# gripper_board.net
KiCad netlist of a schematic drawn in EAGLE
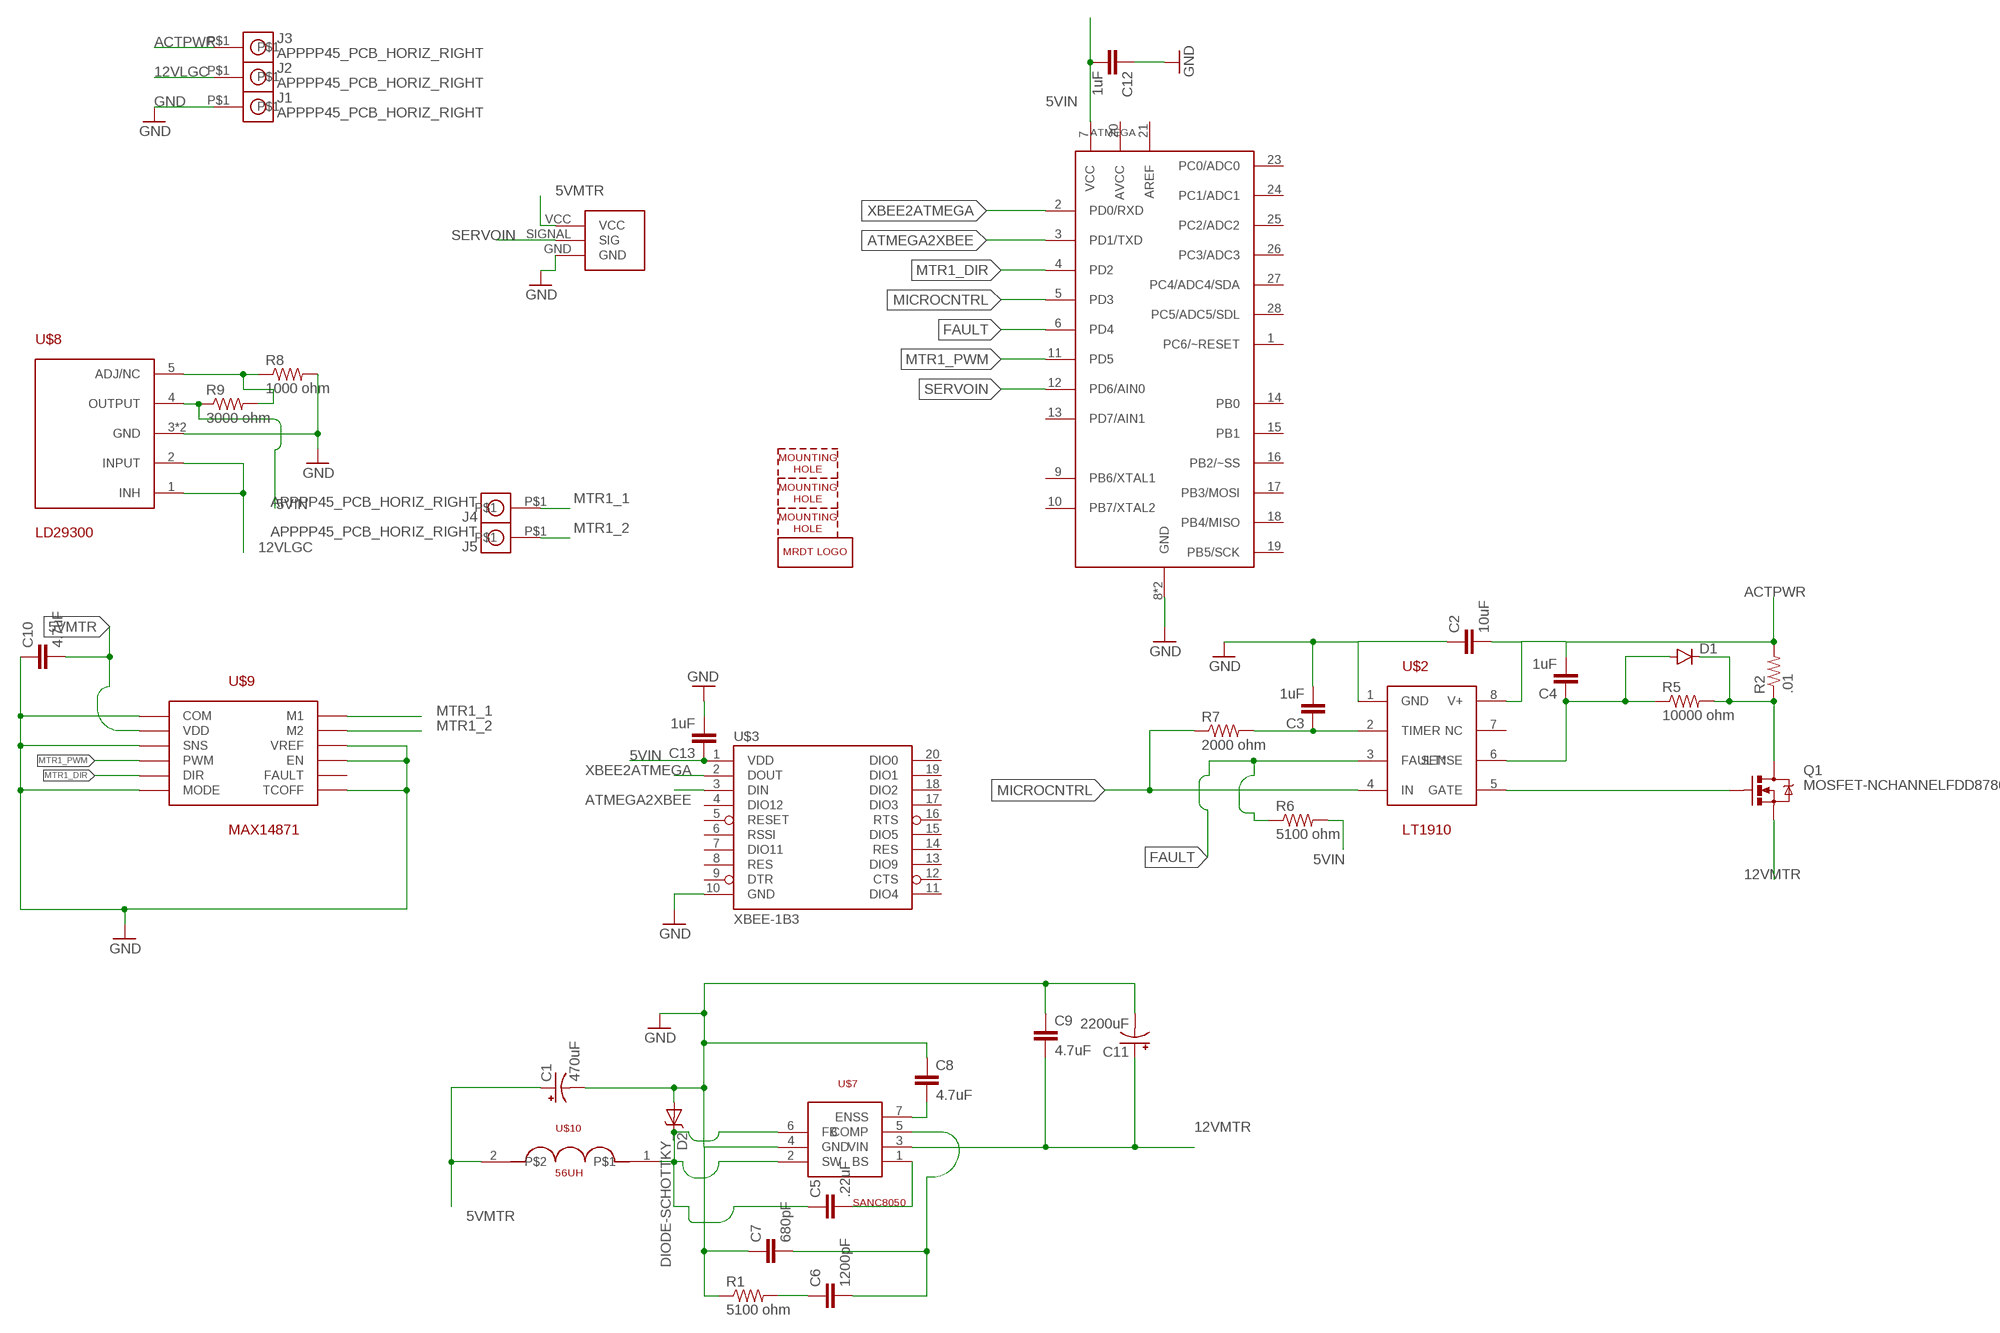
[diagram p0: schematic, sheet 1]

(export (version "E")
  (design (tool "Eeschema 10.0.6"))
  (components
    (comp (ref "ATMEGA")
      (value "Q_ATMEGA328P")
      (footprint "eagle-import:DIP28")
      (libsource (lib "eagle-import") (part "Q_ATMEGA328P"))
    )
    (comp (ref "C1")
      (value "470uF")
      (footprint "eagle-import:PANASONIC_H13")
      (libsource (lib "eagle-import") (part "100UF-ELECT"))
    )
    (comp (ref "C2")
      (value "10uF")
      (footprint "eagle-import:0603-CAP")
      (libsource (lib "eagle-import") (part "CAP0603-CAP"))
    )
    (comp (ref "C3")
      (value "1uF")
      (footprint "eagle-import:0603-CAP")
      (libsource (lib "eagle-import") (part "CAP0603-CAP"))
    )
    (comp (ref "C4")
      (value "1uF")
      (footprint "eagle-import:0603-CAP")
      (libsource (lib "eagle-import") (part "CAP0603-CAP"))
    )
    (comp (ref "C5")
      (value ".22uF")
      (footprint "eagle-import:1206")
      (libsource (lib "eagle-import") (part "1.0UF50V10%(1206)"))
    )
    (comp (ref "C6")
      (value "1200pF")
      (footprint "eagle-import:1206")
      (libsource (lib "eagle-import") (part "1.0UF50V10%(1206)"))
    )
    (comp (ref "C7")
      (value "680pF")
      (footprint "eagle-import:1206")
      (libsource (lib "eagle-import") (part "1.0UF50V10%(1206)"))
    )
    (comp (ref "C8")
      (value "4.7uF")
      (footprint "eagle-import:1206")
      (libsource (lib "eagle-import") (part "1.0UF50V10%(1206)"))
    )
    (comp (ref "C9")
      (value "4.7uF")
      (footprint "eagle-import:1206")
      (libsource (lib "eagle-import") (part "1.0UF50V10%(1206)"))
    )
    (comp (ref "C10")
      (value "4.7uF")
      (footprint "eagle-import:1206")
      (libsource (lib "eagle-import") (part "1.0UF50V10%(1206)"))
    )
    (comp (ref "C11")
      (value "2200uF")
      (footprint "eagle-import:C_16MM")
      (libsource (lib "eagle-import") (part "C_108CKH050M"))
    )
    (comp (ref "C12")
      (value "1uF")
      (footprint "eagle-import:0603-CAP")
      (libsource (lib "eagle-import") (part "CAP0603-CAP"))
    )
    (comp (ref "C13")
      (value "1uF")
      (footprint "eagle-import:0603-CAP")
      (libsource (lib "eagle-import") (part "CAP0603-CAP"))
    )
    (comp (ref "D1")
      (value "DIODESMA")
      (footprint "eagle-import:SMA-DIODE")
      (libsource (lib "eagle-import") (part "DIODESMA"))
    )
    (comp (ref "D2")
      (value "DIODE-SCHOTTKY_")
      (footprint "eagle-import:SMA-DIODE")
      (libsource (lib "eagle-import") (part "DIODE-SCHOTTKY_"))
    )
    (comp (ref "H1")
      (value "MOUNTING_HOLE#4")
      (footprint "eagle-import:#4_SCREW")
      (libsource (lib "eagle-import") (part "MOUNTING_HOLE#4"))
    )
    (comp (ref "H2")
      (value "MOUNTING_HOLE#4")
      (footprint "eagle-import:#4_SCREW")
      (libsource (lib "eagle-import") (part "MOUNTING_HOLE#4"))
    )
    (comp (ref "H3")
      (value "MOUNTING_HOLE#4")
      (footprint "eagle-import:#4_SCREW")
      (libsource (lib "eagle-import") (part "MOUNTING_HOLE#4"))
    )
    (comp (ref "J1")
      (value "APPPP45_PCB_HORIZ_RIGHT")
      (footprint "eagle-import:APP45_PCB_HORIZ_RIGHT")
      (libsource (lib "eagle-import") (part "APPPP45_PCB_HORIZ_RIGHT"))
    )
    (comp (ref "J2")
      (value "APPPP45_PCB_HORIZ_RIGHT")
      (footprint "eagle-import:APP45_PCB_HORIZ_RIGHT")
      (libsource (lib "eagle-import") (part "APPPP45_PCB_HORIZ_RIGHT"))
    )
    (comp (ref "J3")
      (value "APPPP45_PCB_HORIZ_RIGHT")
      (footprint "eagle-import:APP45_PCB_HORIZ_RIGHT")
      (libsource (lib "eagle-import") (part "APPPP45_PCB_HORIZ_RIGHT"))
    )
    (comp (ref "J4")
      (value "APPPP45_PCB_HORIZ_RIGHT")
      (footprint "eagle-import:APP45_PCB_HORIZ_RIGHT")
      (libsource (lib "eagle-import") (part "APPPP45_PCB_HORIZ_RIGHT"))
    )
    (comp (ref "J5")
      (value "APPPP45_PCB_HORIZ_RIGHT")
      (footprint "eagle-import:APP45_PCB_HORIZ_RIGHT")
      (libsource (lib "eagle-import") (part "APPPP45_PCB_HORIZ_RIGHT"))
    )
    (comp (ref "LOGO1")
      (value "MRDT_LOGO")
      (footprint "eagle-import:MRDT_LOGO")
      (libsource (lib "eagle-import") (part "MRDT_LOGO"))
    )
    (comp (ref "Q1")
      (value "MOSFET-NCHANNELFDD8780")
      (footprint "eagle-import:DPAK")
      (libsource (lib "eagle-import") (part "MOSFET-NCHANNELFDD8780"))
    )
    (comp (ref "R1")
      (value "5100 ohm")
      (footprint "eagle-import:0603-RES")
      (libsource (lib "eagle-import") (part "RESISTOR0603-RES"))
    )
    (comp (ref "R2")
      (value ".01")
      (footprint "eagle-import:AXIAL-0.3")
      (libsource (lib "eagle-import") (part "SparkFun-Resistors_RESISTORAXIAL-0.3"))
    )
    (comp (ref "R5")
      (value "10000 ohm")
      (footprint "eagle-import:0603-RES")
      (libsource (lib "eagle-import") (part "RESISTOR0603-RES"))
    )
    (comp (ref "R6")
      (value "5100 ohm")
      (footprint "eagle-import:0603-RES")
      (libsource (lib "eagle-import") (part "RESISTOR0603-RES"))
    )
    (comp (ref "R7")
      (value "2000 ohm")
      (footprint "eagle-import:0603-RES")
      (libsource (lib "eagle-import") (part "RESISTOR0603-RES"))
    )
    (comp (ref "R8")
      (value "1000 ohm")
      (footprint "eagle-import:0603-RES")
      (libsource (lib "eagle-import") (part "RESISTOR0603-RES"))
    )
    (comp (ref "R9")
      (value "3000 ohm")
      (footprint "eagle-import:0603-RES")
      (libsource (lib "eagle-import") (part "RESISTOR0603-RES"))
    )
    (comp (ref "U$1")
      (value "SERVO")
      (footprint "eagle-import:SERVO_JACK")
      (libsource (lib "eagle-import") (part "SERVO"))
    )
    (comp (ref "U$2")
      (value "LT1910")
      (footprint "eagle-import:SOIC8")
      (libsource (lib "eagle-import") (part "LT1910"))
    )
    (comp (ref "U$3")
      (value "XBEE-1B3")
      (footprint "eagle-import:XBEE-SMD")
      (libsource (lib "eagle-import") (part "XBEE-1B3"))
    )
    (comp (ref "U$7")
      (value "SANC8050")
      (footprint "eagle-import:TO-220-7")
      (libsource (lib "eagle-import") (part "SANC8050"))
    )
    (comp (ref "U$8")
      (value "LD29300")
      (footprint "eagle-import:P2PAK")
      (libsource (lib "eagle-import") (part "LD29300"))
    )
    (comp (ref "U$9")
      (value "MAX14871")
      (footprint "eagle-import:TSSOP-16")
      (libsource (lib "eagle-import") (part "MAX14871"))
    )
    (comp (ref "U$10")
      (value "56UH")
      (footprint "eagle-import:1210")
      (libsource (lib "eagle-import") (part "56UH"))
    )
  )
  (nets
    (net (code "1") (name "/5VIN") (class "Default")
      (node (ref "ATMEGA") (pin "7") (pinfunction "VCC_7") (pintype "bidirectional"))
      (node (ref "C12") (pin "2") (pinfunction "2_2") (pintype "passive"))
      (node (ref "C13") (pin "1") (pinfunction "1_1") (pintype "passive"))
      (node (ref "R6") (pin "2") (pinfunction "2_2") (pintype "passive"))
      (node (ref "R9") (pin "1") (pinfunction "1_1") (pintype "passive"))
      (node (ref "U$3") (pin "1") (pinfunction "VDD_1") (pintype "power_in"))
      (node (ref "U$8") (pin "4") (pinfunction "OUTPUT_4") (pintype "bidirectional"))
    )
    (net (code "2") (name "/12VLGC") (class "Default")
      (node (ref "J2") (pin "P$1") (pinfunction "P$1_P$1") (pintype "bidirectional"))
      (node (ref "U$8") (pin "1") (pinfunction "INH_1") (pintype "bidirectional"))
      (node (ref "U$8") (pin "2") (pinfunction "INPUT_2") (pintype "bidirectional"))
    )
    (net (code "3") (name "/12VMTR") (class "Default")
      (node (ref "C11") (pin "+") (pinfunction "+_+") (pintype "passive"))
      (node (ref "C9") (pin "2") (pinfunction "2_2") (pintype "passive"))
      (node (ref "Q1") (pin "3") (pinfunction "S_3") (pintype "passive"))
      (node (ref "U$7") (pin "3") (pinfunction "VIN_3") (pintype "bidirectional"))
    )
    (net (code "4") (name "/ACTPWR") (class "Default")
      (node (ref "C2") (pin "2") (pinfunction "2_2") (pintype "passive"))
      (node (ref "C4") (pin "2") (pinfunction "2_2") (pintype "passive"))
      (node (ref "J3") (pin "P$1") (pinfunction "P$1_P$1") (pintype "bidirectional"))
      (node (ref "R2") (pin "P$2") (pinfunction "2_P$2") (pintype "passive"))
      (node (ref "U$2") (pin "8") (pinfunction "V+_8") (pintype "bidirectional"))
    )
    (net (code "5") (name "/MTR1_1") (class "Default")
      (node (ref "J4") (pin "P$1") (pinfunction "P$1_P$1") (pintype "bidirectional"))
      (node (ref "U$9") (pin "2") (pinfunction "M1_2") (pintype "bidirectional"))
      (node (ref "U$9") (pin "3") (pinfunction "M1_3") (pintype "bidirectional"))
    )
    (net (code "6") (name "/MTR1_2") (class "Default")
      (node (ref "J5") (pin "P$1") (pinfunction "P$1_P$1") (pintype "bidirectional"))
      (node (ref "U$9") (pin "14") (pinfunction "M2_14") (pintype "bidirectional"))
      (node (ref "U$9") (pin "15") (pinfunction "M2_15") (pintype "bidirectional"))
    )
    (net (code "7") (name "5VMTR") (class "Default")
      (node (ref "C1") (pin "+") (pinfunction "+_+") (pintype "passive"))
      (node (ref "C10") (pin "2") (pinfunction "2_2") (pintype "passive"))
      (node (ref "U$1") (pin "VCC") (pinfunction "VCC_VCC") (pintype "bidirectional"))
      (node (ref "U$10") (pin "2") (pinfunction "P$2_2") (pintype "bidirectional"))
      (node (ref "U$9") (pin "13") (pinfunction "VDD_13") (pintype "bidirectional"))
      (node (ref "U$9") (pin "4") (pinfunction "VDD_4") (pintype "bidirectional"))
    )
    (net (code "8") (name "ATMEGA2XBEE") (class "Default")
      (node (ref "ATMEGA") (pin "3") (pinfunction "PD1/TXD_3") (pintype "bidirectional"))
      (node (ref "U$3") (pin "3") (pinfunction "DIN_3") (pintype "input"))
    )
    (net (code "9") (name "FAULT") (class "Default")
      (node (ref "ATMEGA") (pin "6") (pinfunction "PD4_6") (pintype "bidirectional"))
      (node (ref "R6") (pin "1") (pinfunction "1_1") (pintype "passive"))
      (node (ref "U$2") (pin "3") (pinfunction "FAULT*_3") (pintype "bidirectional"))
    )
    (net (code "10") (name "GND") (class "Default")
      (node (ref "ATMEGA") (pin "22") (pinfunction "GND_22") (pintype "bidirectional"))
      (node (ref "ATMEGA") (pin "8") (pinfunction "GND_8") (pintype "bidirectional"))
      (node (ref "C1") (pin "-") (pinfunction "-_-") (pintype "passive"))
      (node (ref "C10") (pin "1") (pinfunction "1_1") (pintype "passive"))
      (node (ref "C11") (pin "GND") (pinfunction "-_GND") (pintype "passive"))
      (node (ref "C12") (pin "1") (pinfunction "1_1") (pintype "passive"))
      (node (ref "C13") (pin "2") (pinfunction "2_2") (pintype "passive"))
      (node (ref "C2") (pin "1") (pinfunction "1_1") (pintype "passive"))
      (node (ref "C3") (pin "2") (pinfunction "2_2") (pintype "passive"))
      (node (ref "C7") (pin "1") (pinfunction "1_1") (pintype "passive"))
      (node (ref "C8") (pin "1") (pinfunction "1_1") (pintype "passive"))
      (node (ref "C9") (pin "1") (pinfunction "1_1") (pintype "passive"))
      (node (ref "D2") (pin "A") (pinfunction "A_A") (pintype "passive"))
      (node (ref "J1") (pin "P$1") (pinfunction "P$1_P$1") (pintype "bidirectional"))
      (node (ref "R1") (pin "1") (pinfunction "1_1") (pintype "passive"))
      (node (ref "R8") (pin "2") (pinfunction "2_2") (pintype "passive"))
      (node (ref "U$1") (pin "GND") (pinfunction "GND_GND") (pintype "bidirectional"))
      (node (ref "U$2") (pin "1") (pinfunction "GND_1") (pintype "bidirectional"))
      (node (ref "U$3") (pin "10") (pinfunction "GND_10") (pintype "power_in"))
      (node (ref "U$7") (pin "4") (pinfunction "GND_4") (pintype "bidirectional"))
      (node (ref "U$8") (pin "3") (pinfunction "GND_3") (pintype "bidirectional"))
      (node (ref "U$8") (pin "P$1") (pinfunction "GND_P$1") (pintype "bidirectional"))
      (node (ref "U$9") (pin "1") (pinfunction "COM_1") (pintype "bidirectional"))
      (node (ref "U$9") (pin "11") (pinfunction "EN_11") (pintype "bidirectional"))
      (node (ref "U$9") (pin "12") (pinfunction "VREF_12") (pintype "bidirectional"))
      (node (ref "U$9") (pin "16") (pinfunction "COM_16") (pintype "bidirectional"))
      (node (ref "U$9") (pin "5") (pinfunction "SNS_5") (pintype "bidirectional"))
      (node (ref "U$9") (pin "8") (pinfunction "MODE_8") (pintype "bidirectional"))
      (node (ref "U$9") (pin "9") (pinfunction "TCOFF_9") (pintype "bidirectional"))
    )
    (net (code "11") (name "MICROCNTRL") (class "Default")
      (node (ref "ATMEGA") (pin "5") (pinfunction "PD3_5") (pintype "bidirectional"))
      (node (ref "R7") (pin "1") (pinfunction "1_1") (pintype "passive"))
      (node (ref "U$2") (pin "4") (pinfunction "IN_4") (pintype "bidirectional"))
    )
    (net (code "12") (name "MTR1_DIR") (class "Default")
      (node (ref "ATMEGA") (pin "4") (pinfunction "PD2_4") (pintype "bidirectional"))
      (node (ref "U$9") (pin "7") (pinfunction "DIR_7") (pintype "bidirectional"))
    )
    (net (code "13") (name "MTR1_PWM") (class "Default")
      (node (ref "ATMEGA") (pin "11") (pinfunction "PD5_11") (pintype "bidirectional"))
      (node (ref "U$9") (pin "6") (pinfunction "PWM_6") (pintype "bidirectional"))
    )
    (net (code "14") (name "Net-(C6-Pad1)") (class "Default")
      (node (ref "C6") (pin "1") (pinfunction "1_1") (pintype "passive"))
      (node (ref "R1") (pin "2") (pinfunction "2_2") (pintype "passive"))
    )
    (net (code "15") (name "Net-(Q1-D)") (class "Default")
      (node (ref "D1") (pin "C") (pinfunction "C_C") (pintype "passive"))
      (node (ref "Q1") (pin "4") (pinfunction "D_4") (pintype "passive"))
      (node (ref "R2") (pin "P$1") (pinfunction "1_P$1") (pintype "passive"))
      (node (ref "R5") (pin "2") (pinfunction "2_2") (pintype "passive"))
    )
    (net (code "16") (name "Net-(Q1-G)") (class "Default")
      (node (ref "Q1") (pin "1") (pinfunction "G_1") (pintype "passive"))
      (node (ref "U$2") (pin "5") (pinfunction "GATE_5") (pintype "bidirectional"))
    )
    (net (code "17") (name "Net-(U$2-SENSE)") (class "Default")
      (node (ref "C4") (pin "1") (pinfunction "1_1") (pintype "passive"))
      (node (ref "D1") (pin "A") (pinfunction "A_A") (pintype "passive"))
      (node (ref "R5") (pin "1") (pinfunction "1_1") (pintype "passive"))
      (node (ref "U$2") (pin "6") (pinfunction "SENSE_6") (pintype "bidirectional"))
    )
    (net (code "18") (name "Net-(U$2-TIMER)") (class "Default")
      (node (ref "C3") (pin "1") (pinfunction "1_1") (pintype "passive"))
      (node (ref "R7") (pin "2") (pinfunction "2_2") (pintype "passive"))
      (node (ref "U$2") (pin "2") (pinfunction "TIMER_2") (pintype "bidirectional"))
    )
    (net (code "19") (name "Net-(U$7-BS)") (class "Default")
      (node (ref "C5") (pin "2") (pinfunction "2_2") (pintype "passive"))
      (node (ref "U$7") (pin "1") (pinfunction "BS_1") (pintype "bidirectional"))
    )
    (net (code "20") (name "Net-(U$7-COMP)") (class "Default")
      (node (ref "C6") (pin "2") (pinfunction "2_2") (pintype "passive"))
      (node (ref "C7") (pin "2") (pinfunction "2_2") (pintype "passive"))
      (node (ref "U$7") (pin "5") (pinfunction "COMP_5") (pintype "bidirectional"))
    )
    (net (code "21") (name "Net-(U$7-ENSS)") (class "Default")
      (node (ref "C8") (pin "2") (pinfunction "2_2") (pintype "passive"))
      (node (ref "U$7") (pin "7") (pinfunction "ENSS_7") (pintype "bidirectional"))
    )
    (net (code "22") (name "Net-(U$8-ADJ{slash}NC)") (class "Default")
      (node (ref "R8") (pin "1") (pinfunction "1_1") (pintype "passive"))
      (node (ref "R9") (pin "2") (pinfunction "2_2") (pintype "passive"))
      (node (ref "U$8") (pin "5") (pinfunction "ADJ/NC_5") (pintype "bidirectional"))
    )
    (net (code "23") (name "Net-(U$10-P$1)") (class "Default")
      (node (ref "C5") (pin "1") (pinfunction "1_1") (pintype "passive"))
      (node (ref "D2") (pin "C") (pinfunction "C_C") (pintype "passive"))
      (node (ref "U$10") (pin "1") (pinfunction "P$1_1") (pintype "bidirectional"))
      (node (ref "U$7") (pin "2") (pinfunction "SW_2") (pintype "bidirectional"))
      (node (ref "U$7") (pin "6") (pinfunction "FB_6") (pintype "bidirectional"))
    )
    (net (code "24") (name "SERVOIN") (class "Default")
      (node (ref "ATMEGA") (pin "12") (pinfunction "PD6/AIN0_12") (pintype "bidirectional"))
      (node (ref "U$1") (pin "SIGNAL") (pinfunction "SIG_SIGNAL") (pintype "bidirectional"))
    )
    (net (code "25") (name "XBEE2ATMEGA") (class "Default")
      (node (ref "ATMEGA") (pin "2") (pinfunction "PD0/RXD_2") (pintype "bidirectional"))
      (node (ref "U$3") (pin "2") (pinfunction "DOUT_2") (pintype "output"))
    )
    (net (code "26") (name "unconnected-(ATMEGA-AREF-Pad21)") (class "Default")
      (node (ref "ATMEGA") (pin "21") (pinfunction "AREF_21") (pintype "bidirectional"))
    )
    (net (code "27") (name "unconnected-(ATMEGA-AVCC-Pad20)") (class "Default")
      (node (ref "ATMEGA") (pin "20") (pinfunction "AVCC_20") (pintype "bidirectional"))
    )
    (net (code "28") (name "unconnected-(ATMEGA-PB0-Pad14)") (class "Default")
      (node (ref "ATMEGA") (pin "14") (pinfunction "PB0_14") (pintype "bidirectional"))
    )
    (net (code "29") (name "unconnected-(ATMEGA-PB1-Pad15)") (class "Default")
      (node (ref "ATMEGA") (pin "15") (pinfunction "PB1_15") (pintype "bidirectional"))
    )
    (net (code "30") (name "unconnected-(ATMEGA-PB2{slash}~{SS}-Pad16)") (class "Default")
      (node (ref "ATMEGA") (pin "16") (pinfunction "PB2/~{SS}_16") (pintype "bidirectional"))
    )
    (net (code "31") (name "unconnected-(ATMEGA-PB3{slash}MOSI-Pad17)") (class "Default")
      (node (ref "ATMEGA") (pin "17") (pinfunction "PB3/MOSI_17") (pintype "bidirectional"))
    )
    (net (code "32") (name "unconnected-(ATMEGA-PB4{slash}MISO-Pad18)") (class "Default")
      (node (ref "ATMEGA") (pin "18") (pinfunction "PB4/MISO_18") (pintype "bidirectional"))
    )
    (net (code "33") (name "unconnected-(ATMEGA-PB5{slash}SCK-Pad19)") (class "Default")
      (node (ref "ATMEGA") (pin "19") (pinfunction "PB5/SCK_19") (pintype "bidirectional"))
    )
    (net (code "34") (name "unconnected-(ATMEGA-PB6{slash}XTAL1-Pad9)") (class "Default")
      (node (ref "ATMEGA") (pin "9") (pinfunction "PB6/XTAL1_9") (pintype "bidirectional"))
    )
    (net (code "35") (name "unconnected-(ATMEGA-PB7{slash}XTAL2-Pad10)") (class "Default")
      (node (ref "ATMEGA") (pin "10") (pinfunction "PB7/XTAL2_10") (pintype "bidirectional"))
    )
    (net (code "36") (name "unconnected-(ATMEGA-PC0{slash}ADC0-Pad23)") (class "Default")
      (node (ref "ATMEGA") (pin "23") (pinfunction "PC0/ADC0_23") (pintype "bidirectional"))
    )
    (net (code "37") (name "unconnected-(ATMEGA-PC1{slash}ADC1-Pad24)") (class "Default")
      (node (ref "ATMEGA") (pin "24") (pinfunction "PC1/ADC1_24") (pintype "bidirectional"))
    )
    (net (code "38") (name "unconnected-(ATMEGA-PC2{slash}ADC2-Pad25)") (class "Default")
      (node (ref "ATMEGA") (pin "25") (pinfunction "PC2/ADC2_25") (pintype "bidirectional"))
    )
    (net (code "39") (name "unconnected-(ATMEGA-PC3{slash}ADC3-Pad26)") (class "Default")
      (node (ref "ATMEGA") (pin "26") (pinfunction "PC3/ADC3_26") (pintype "bidirectional"))
    )
    (net (code "40") (name "unconnected-(ATMEGA-PC4{slash}ADC4{slash}SDA-Pad27)") (class "Default")
      (node (ref "ATMEGA") (pin "27") (pinfunction "PC4/ADC4/SDA_27") (pintype "bidirectional"))
    )
    (net (code "41") (name "unconnected-(ATMEGA-PC5{slash}ADC5{slash}SDL-Pad28)") (class "Default")
      (node (ref "ATMEGA") (pin "28") (pinfunction "PC5/ADC5/SDL_28") (pintype "bidirectional"))
    )
    (net (code "42") (name "unconnected-(ATMEGA-PC6{slash}~{RESET}-Pad1)") (class "Default")
      (node (ref "ATMEGA") (pin "1") (pinfunction "PC6/~{RESET}_1") (pintype "bidirectional"))
    )
    (net (code "43") (name "unconnected-(ATMEGA-PD7{slash}AIN1-Pad13)") (class "Default")
      (node (ref "ATMEGA") (pin "13") (pinfunction "PD7/AIN1_13") (pintype "bidirectional"))
    )
    (net (code "44") (name "unconnected-(U$2-NC-Pad7)") (class "Default")
      (node (ref "U$2") (pin "7") (pinfunction "NC_7") (pintype "bidirectional"))
    )
    (net (code "45") (name "unconnected-(U$3-CTS-Pad12)") (class "Default")
      (node (ref "U$3") (pin "12") (pinfunction "CTS_12") (pintype "output"))
    )
    (net (code "46") (name "unconnected-(U$3-DIO0-Pad20)") (class "Default")
      (node (ref "U$3") (pin "20") (pinfunction "DIO0_20") (pintype "bidirectional"))
    )
    (net (code "47") (name "unconnected-(U$3-DIO1-Pad19)") (class "Default")
      (node (ref "U$3") (pin "19") (pinfunction "DIO1_19") (pintype "bidirectional"))
    )
    (net (code "48") (name "unconnected-(U$3-DIO2-Pad18)") (class "Default")
      (node (ref "U$3") (pin "18") (pinfunction "DIO2_18") (pintype "bidirectional"))
    )
    (net (code "49") (name "unconnected-(U$3-DIO3-Pad17)") (class "Default")
      (node (ref "U$3") (pin "17") (pinfunction "DIO3_17") (pintype "bidirectional"))
    )
    (net (code "50") (name "unconnected-(U$3-DIO4-Pad11)") (class "Default")
      (node (ref "U$3") (pin "11") (pinfunction "DIO4_11") (pintype "bidirectional"))
    )
    (net (code "51") (name "unconnected-(U$3-DIO5-Pad15)") (class "Default")
      (node (ref "U$3") (pin "15") (pinfunction "DIO5_15") (pintype "bidirectional"))
    )
    (net (code "52") (name "unconnected-(U$3-DIO9-Pad13)") (class "Default")
      (node (ref "U$3") (pin "13") (pinfunction "DIO9_13") (pintype "bidirectional"))
    )
    (net (code "53") (name "unconnected-(U$3-DIO11-Pad7)") (class "Default")
      (node (ref "U$3") (pin "7") (pinfunction "DIO11_7") (pintype "bidirectional"))
    )
    (net (code "54") (name "unconnected-(U$3-DIO12-Pad4)") (class "Default")
      (node (ref "U$3") (pin "4") (pinfunction "DIO12_4") (pintype "bidirectional"))
    )
    (net (code "55") (name "unconnected-(U$3-DTR-Pad9)") (class "Default")
      (node (ref "U$3") (pin "9") (pinfunction "DTR_9") (pintype "bidirectional"))
    )
    (net (code "56") (name "unconnected-(U$3-RES-Pad8)") (class "Default")
      (node (ref "U$3") (pin "8") (pinfunction "RES_8") (pintype "bidirectional"))
    )
    (net (code "57") (name "unconnected-(U$3-RES-Pad14)") (class "Default")
      (node (ref "U$3") (pin "14") (pinfunction "RES_14") (pintype "bidirectional"))
    )
    (net (code "58") (name "unconnected-(U$3-RESET-Pad5)") (class "Default")
      (node (ref "U$3") (pin "5") (pinfunction "RESET_5") (pintype "input"))
    )
    (net (code "59") (name "unconnected-(U$3-RSSI-Pad6)") (class "Default")
      (node (ref "U$3") (pin "6") (pinfunction "RSSI_6") (pintype "bidirectional"))
    )
    (net (code "60") (name "unconnected-(U$3-RTS-Pad16)") (class "Default")
      (node (ref "U$3") (pin "16") (pinfunction "RTS_16") (pintype "input"))
    )
    (net (code "61") (name "unconnected-(U$9-FAULT-Pad10)") (class "Default")
      (node (ref "U$9") (pin "10") (pinfunction "FAULT_10") (pintype "bidirectional"))
    )
  )
)
